# chess_module_HEF.net
KiCad netlist of a schematic drawn in Altium Designer
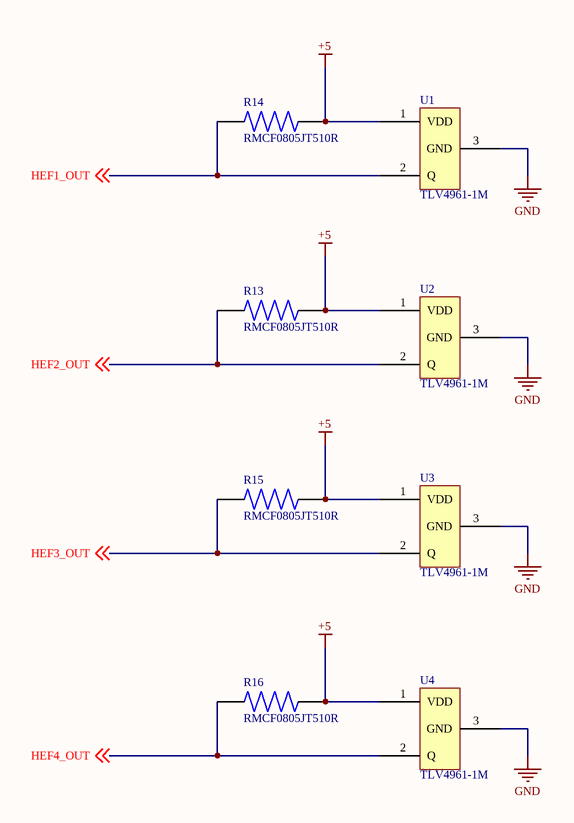
[diagram p0: chess_module_HEF.SchDoc]

(export (version "E")
  (design (tool "Eeschema 10.0.6"))
  (components
    (comp (ref "R13")
      (value "RMCF0805JT510R")
      (footprint "RESC2012X65N:RESC2012X65N")
      (libsource (lib "chess_module") (part "RMCF0805JT510R"))
    )
    (comp (ref "R14")
      (value "RMCF0805JT510R")
      (footprint "RESC2012X65N:RESC2012X65N")
      (libsource (lib "chess_module") (part "RMCF0805JT510R"))
    )
    (comp (ref "R15")
      (value "RMCF0805JT510R")
      (footprint "RESC2012X65N:RESC2012X65N")
      (libsource (lib "chess_module") (part "RMCF0805JT510R"))
    )
    (comp (ref "R16")
      (value "RMCF0805JT510R")
      (footprint "RESC2012X65N:RESC2012X65N")
      (libsource (lib "chess_module") (part "RMCF0805JT510R"))
    )
    (comp (ref "U1")
      (value "TLV4961-1M")
      (footprint "SOT95P245X110-3N")
      (description "Hall Effect Sensor")
      (libsource (lib "chess_module") (part "TLV4961-1M"))
    )
    (comp (ref "U2")
      (value "TLV4961-1M")
      (footprint "SOT95P245X110-3N")
      (description "Hall Effect Sensor")
      (libsource (lib "chess_module") (part "TLV4961-1M"))
    )
    (comp (ref "U3")
      (value "TLV4961-1M")
      (footprint "SOT95P245X110-3N")
      (description "Hall Effect Sensor")
      (libsource (lib "chess_module") (part "TLV4961-1M"))
    )
    (comp (ref "U4")
      (value "TLV4961-1M")
      (footprint "SOT95P245X110-3N")
      (description "Hall Effect Sensor")
      (libsource (lib "chess_module") (part "TLV4961-1M"))
    )
  )
  (nets
    (net (code "1") (name "+5") (class "Default")
      (node (ref "R13") (pin "2") (pinfunction "2_2") (pintype "passive"))
      (node (ref "R14") (pin "2") (pinfunction "2_2") (pintype "passive"))
      (node (ref "R15") (pin "2") (pinfunction "2_2") (pintype "passive"))
      (node (ref "R16") (pin "2") (pinfunction "2_2") (pintype "passive"))
      (node (ref "U1") (pin "1") (pinfunction "VDD_1") (pintype "passive"))
      (node (ref "U2") (pin "1") (pinfunction "VDD_1") (pintype "passive"))
      (node (ref "U3") (pin "1") (pinfunction "VDD_1") (pintype "passive"))
      (node (ref "U4") (pin "1") (pinfunction "VDD_1") (pintype "passive"))
    )
    (net (code "2") (name "GND") (class "Default")
      (node (ref "U1") (pin "3") (pinfunction "GND_3") (pintype "passive"))
      (node (ref "U2") (pin "3") (pinfunction "GND_3") (pintype "passive"))
      (node (ref "U3") (pin "3") (pinfunction "GND_3") (pintype "passive"))
      (node (ref "U4") (pin "3") (pinfunction "GND_3") (pintype "passive"))
    )
    (net (code "3") (name "HEF1_OUT") (class "Default")
      (node (ref "R14") (pin "1") (pinfunction "1_1") (pintype "passive"))
      (node (ref "U1") (pin "2") (pinfunction "Q_2") (pintype "passive"))
    )
    (net (code "4") (name "HEF2_OUT") (class "Default")
      (node (ref "R13") (pin "1") (pinfunction "1_1") (pintype "passive"))
      (node (ref "U2") (pin "2") (pinfunction "Q_2") (pintype "passive"))
    )
    (net (code "5") (name "HEF3_OUT") (class "Default")
      (node (ref "R15") (pin "1") (pinfunction "1_1") (pintype "passive"))
      (node (ref "U3") (pin "2") (pinfunction "Q_2") (pintype "passive"))
    )
    (net (code "6") (name "HEF4_OUT") (class "Default")
      (node (ref "R16") (pin "1") (pinfunction "1_1") (pintype "passive"))
      (node (ref "U4") (pin "2") (pinfunction "Q_2") (pintype "passive"))
    )
  )
)
